# totalizer2020.net
KiCad netlist of a schematic drawn in EAGLE
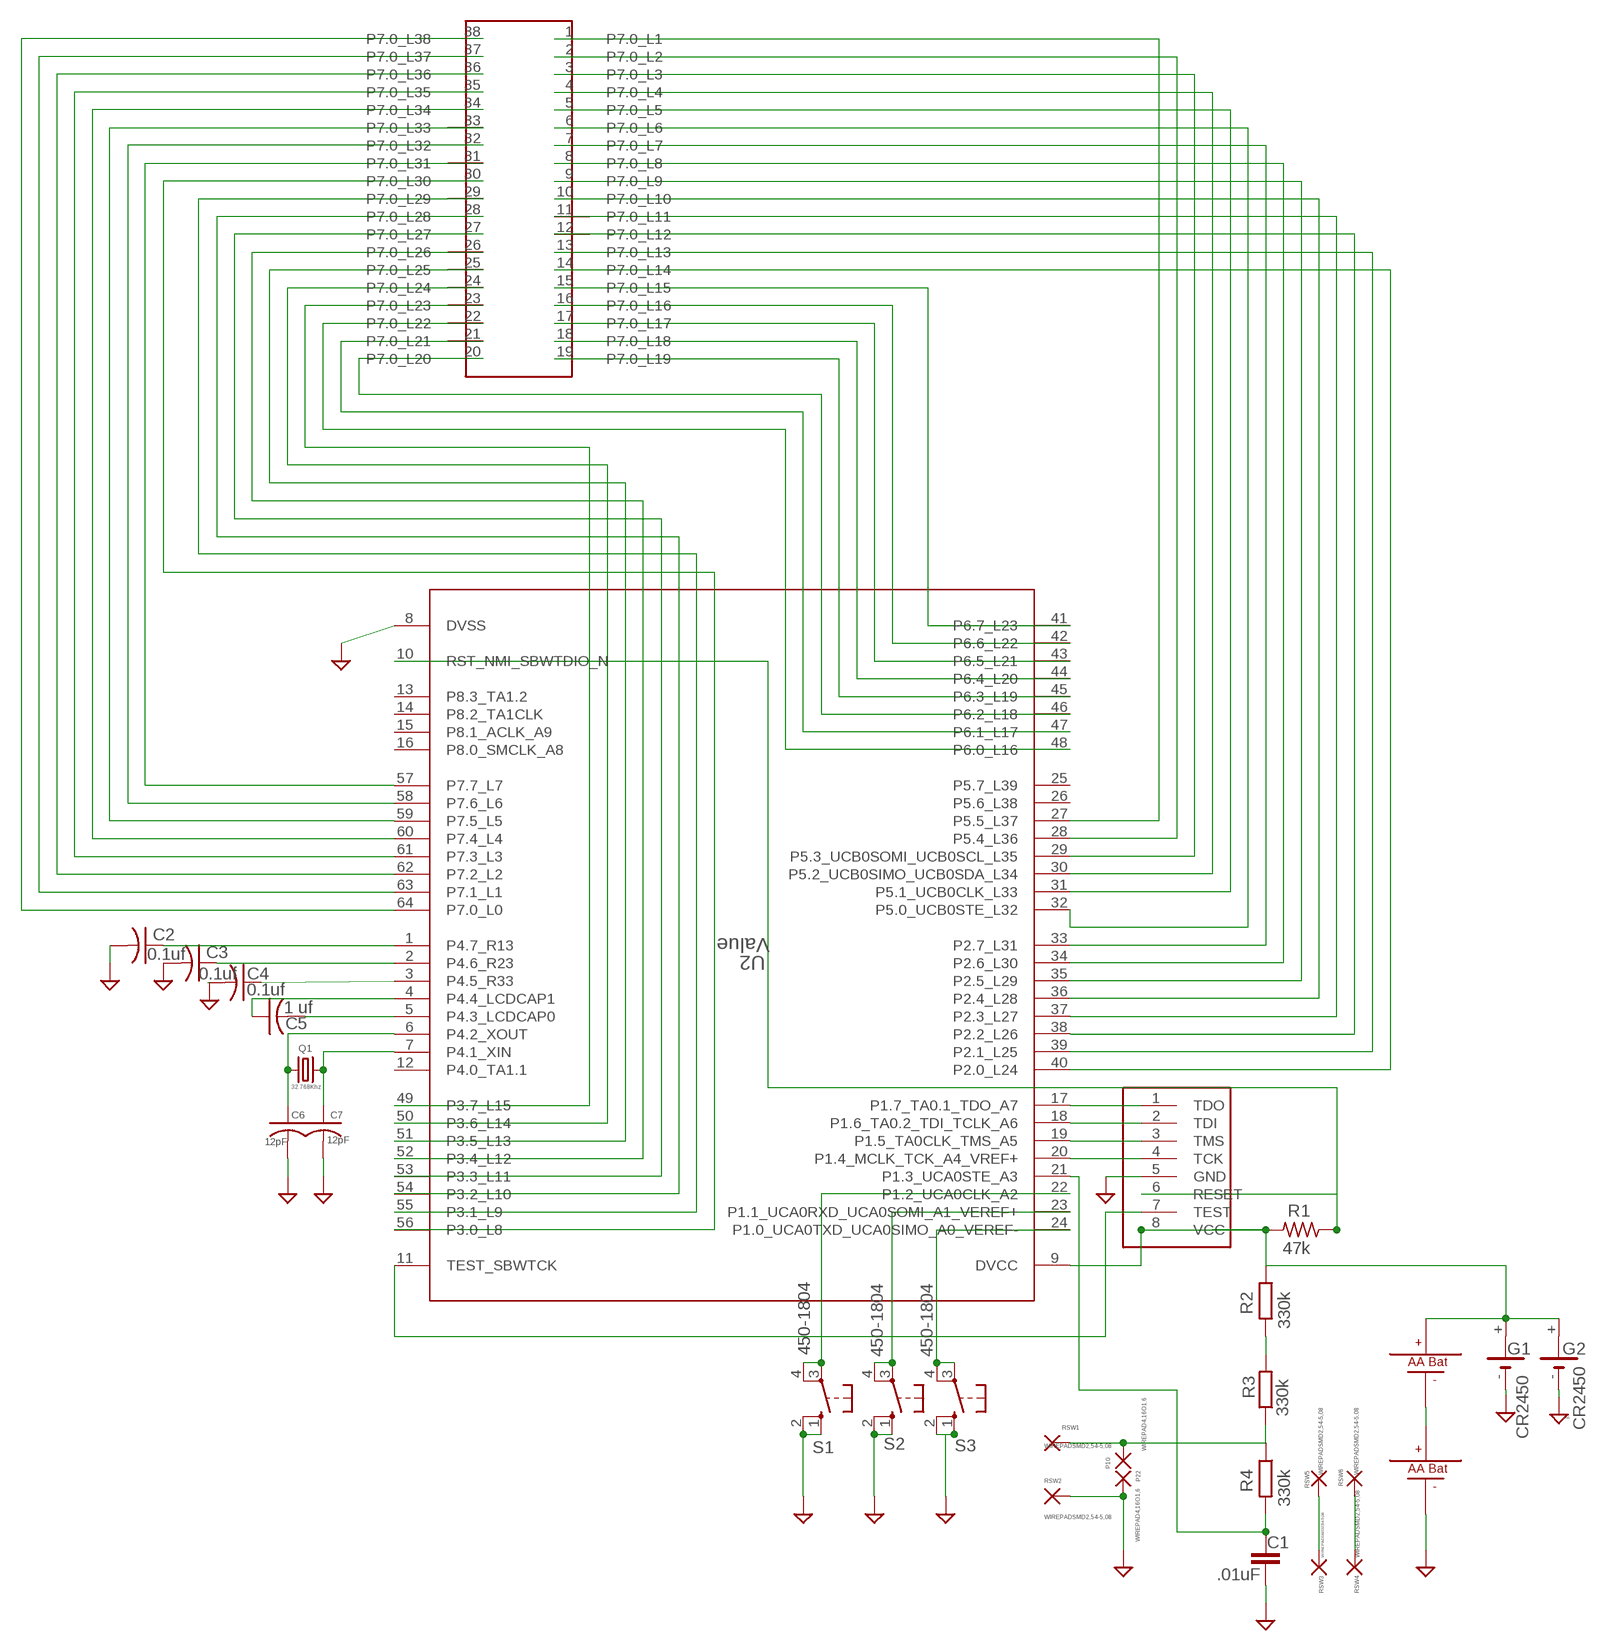
[diagram p0: schematic, sheet 1]

(export (version "E")
  (design (tool "Eeschema 10.0.6"))
  (components
    (comp (ref "8PINCONNECTOR")
      (value "JST-8JST-8")
      (footprint "eagle-import:HDRVR8W64P150_1X8_1200X350X500B")
      (libsource (lib "eagle-import") (part "JST-8JST-8"))
    )
    (comp (ref "C1")
      (value ".01uF")
      (footprint "eagle-import:C0805")
      (libsource (lib "eagle-import") (part "C-EUC0805"))
    )
    (comp (ref "C2")
      (value "0.1uf")
      (footprint "eagle-import:C0805")
      (libsource (lib "eagle-import") (part "C-USC0805"))
    )
    (comp (ref "C3")
      (value "0.1uf")
      (footprint "eagle-import:C0805")
      (libsource (lib "eagle-import") (part "C-USC0805"))
    )
    (comp (ref "C4")
      (value "0.1uf")
      (footprint "eagle-import:C0805")
      (libsource (lib "eagle-import") (part "C-USC0805"))
    )
    (comp (ref "C5")
      (value "1 uf")
      (footprint "eagle-import:C0805")
      (libsource (lib "eagle-import") (part "C-USC0805"))
    )
    (comp (ref "C6")
      (value "12pF")
      (footprint "eagle-import:C0805")
      (libsource (lib "eagle-import") (part "resistor_348_C-USC0805"))
    )
    (comp (ref "C7")
      (value "12pF")
      (footprint "eagle-import:C0805")
      (libsource (lib "eagle-import") (part "resistor_348_C-USC0805"))
    )
    (comp (ref "G1")
      (value "CR2450")
      (footprint "eagle-import:CR2430H")
      (libsource (lib "eagle-import") (part "CR2430H"))
    )
    (comp (ref "G2")
      (value "CR2450")
      (footprint "eagle-import:CR2430H")
      (libsource (lib "eagle-import") (part "CR2430H"))
    )
    (comp (ref "P10")
      (value "WIREPAD4,16O1,6")
      (footprint "eagle-import:4,16O1,6")
      (libsource (lib "eagle-import") (part "WIREPAD4,16O1,6"))
    )
    (comp (ref "P22")
      (value "WIREPAD4,16O1,6")
      (footprint "eagle-import:4,16O1,6")
      (libsource (lib "eagle-import") (part "WIREPAD4,16O1,6"))
    )
    (comp (ref "Q1")
      (value "32.768Khz")
      (footprint "eagle-import:3.2X1.5")
      (libsource (lib "eagle-import") (part "KX-327-NHT"))
    )
    (comp (ref "R1")
      (value "47k")
      (footprint "eagle-import:R0805")
      (libsource (lib "eagle-import") (part "R-US_R0805"))
    )
    (comp (ref "R2")
      (value "330k")
      (footprint "eagle-import:R0805")
      (libsource (lib "eagle-import") (part "R-R0805"))
    )
    (comp (ref "R3")
      (value "330k")
      (footprint "eagle-import:R0805")
      (libsource (lib "eagle-import") (part "R-R0805"))
    )
    (comp (ref "R4")
      (value "330k")
      (footprint "eagle-import:R0805")
      (libsource (lib "eagle-import") (part "R-R0805"))
    )
    (comp (ref "RSW1")
      (value "WIREPADSMD2,54-5,08")
      (footprint "eagle-import:SMD2,54-5,08")
      (libsource (lib "eagle-import") (part "WIREPADSMD2,54-5,08"))
    )
    (comp (ref "RSW2")
      (value "WIREPADSMD2,54-5,08")
      (footprint "eagle-import:SMD2,54-5,08")
      (libsource (lib "eagle-import") (part "WIREPADSMD2,54-5,08"))
    )
    (comp (ref "RSW3")
      (value "WIREPADSMD2,54-5,08")
      (footprint "eagle-import:SMD2,54-5,08")
      (libsource (lib "eagle-import") (part "WIREPADSMD2,54-5,08"))
    )
    (comp (ref "RSW4")
      (value "WIREPADSMD2,54-5,08")
      (footprint "eagle-import:SMD2,54-5,08")
      (libsource (lib "eagle-import") (part "WIREPADSMD2,54-5,08"))
    )
    (comp (ref "RSW5")
      (value "WIREPADSMD2,54-5,08")
      (footprint "eagle-import:SMD2,54-5,08")
      (libsource (lib "eagle-import") (part "WIREPADSMD2,54-5,08"))
    )
    (comp (ref "RSW6")
      (value "WIREPADSMD2,54-5,08")
      (footprint "eagle-import:SMD2,54-5,08")
      (libsource (lib "eagle-import") (part "WIREPADSMD2,54-5,08"))
    )
    (comp (ref "S1")
      (value "450-1804")
      (footprint "eagle-import:B3F-10XX")
      (fields (field (name "MPN") "B3F-1000"))
      (libsource (lib "eagle-import") (part "10-XX"))
    )
    (comp (ref "S2")
      (value "450-1804")
      (footprint "eagle-import:B3F-10XX")
      (fields (field (name "MPN") "B3F-1000"))
      (libsource (lib "eagle-import") (part "10-XX"))
    )
    (comp (ref "S3")
      (value "450-1804")
      (footprint "eagle-import:B3F-10XX")
      (fields (field (name "MPN") "B3F-1000"))
      (libsource (lib "eagle-import") (part "10-XX"))
    )
    (comp (ref "U$1")
      (value "LCD-38LCD-38")
      (footprint "eagle-import:DIP7140W53P200L5505H450Q38B")
      (libsource (lib "eagle-import") (part "LCD-38LCD-38"))
    )
    (comp (ref "U$2")
      (value "AA_BATTERY")
      (footprint "eagle-import:AA_BATTERY")
      (libsource (lib "eagle-import") (part "AA_BATTERY"))
    )
    (comp (ref "U$3")
      (value "AA_BATTERY")
      (footprint "eagle-import:AA_BATTERY")
      (libsource (lib "eagle-import") (part "AA_BATTERY"))
    )
    (comp (ref "U2")
      (value "Value")
      (footprint "eagle-import:PM0064A_N")
      (fields
        (field (name "ALTERNATEPARTNUMBER") "MSP430FR4133IPM")
        (field (name "MANUFACTURER") "Texas Instruments")
        (field (name "PARTNUMBER") "MSP430FR4133IPMR")
      )
      (libsource (lib "eagle-import") (part "MSP430FR4133IPMR"))
    )
  )
  (nets
    (net (code "1") (name "GND") (class "Default")
      (node (ref "8PINCONNECTOR") (pin "5") (pinfunction "GND_5") (pintype "power_in"))
      (node (ref "C1") (pin "1") (pinfunction "1_1") (pintype "passive"))
      (node (ref "C2") (pin "2") (pinfunction "2_2") (pintype "passive"))
      (node (ref "C3") (pin "2") (pinfunction "2_2") (pintype "passive"))
      (node (ref "C4") (pin "2") (pinfunction "2_2") (pintype "passive"))
      (node (ref "C6") (pin "2") (pinfunction "2_2") (pintype "passive"))
      (node (ref "C7") (pin "2") (pinfunction "2_2") (pintype "passive"))
      (node (ref "G1") (pin "-") (pinfunction "-_-") (pintype "passive"))
      (node (ref "G2") (pin "-") (pinfunction "-_-") (pintype "passive"))
      (node (ref "P22") (pin "1") (pinfunction "P_1") (pintype "passive"))
      (node (ref "RSW2") (pin "1") (pinfunction "P_1") (pintype "passive"))
      (node (ref "S1") (pin "1") (pinfunction "S_1") (pintype "passive"))
      (node (ref "S1") (pin "2") (pinfunction "S1_2") (pintype "passive"))
      (node (ref "S2") (pin "1") (pinfunction "S_1") (pintype "passive"))
      (node (ref "S2") (pin "2") (pinfunction "S1_2") (pintype "passive"))
      (node (ref "S3") (pin "1") (pinfunction "S_1") (pintype "passive"))
      (node (ref "S3") (pin "2") (pinfunction "S1_2") (pintype "passive"))
      (node (ref "U$3") (pin "3") (pinfunction "BAT_-_3") (pintype "power_in"))
      (node (ref "U$3") (pin "4") (pinfunction "BAT_-_4") (pintype "power_in"))
      (node (ref "U2") (pin "8") (pinfunction "DVSS_8") (pintype "power_in"))
    )
    (net (code "2") (name "Net-(8PINCONNECTOR-RESET)") (class "Default")
      (node (ref "8PINCONNECTOR") (pin "6") (pinfunction "RESET_6") (pintype "bidirectional"))
      (node (ref "R1") (pin "1") (pinfunction "1_1") (pintype "passive"))
      (node (ref "U2") (pin "10") (pinfunction "RST_NMI_SBWTDIO_N_10") (pintype "input"))
    )
    (net (code "3") (name "Net-(8PINCONNECTOR-TCK)") (class "Default")
      (node (ref "8PINCONNECTOR") (pin "4") (pinfunction "TCK_4") (pintype "bidirectional"))
      (node (ref "U2") (pin "20") (pinfunction "P1.4_MCLK_TCK_A4_VREF+_20") (pintype "bidirectional"))
    )
    (net (code "4") (name "Net-(8PINCONNECTOR-TDI)") (class "Default")
      (node (ref "8PINCONNECTOR") (pin "2") (pinfunction "TDI_2") (pintype "bidirectional"))
      (node (ref "U2") (pin "18") (pinfunction "P1.6_TA0.2_TDI_TCLK_A6_18") (pintype "bidirectional"))
    )
    (net (code "5") (name "Net-(8PINCONNECTOR-TDO)") (class "Default")
      (node (ref "8PINCONNECTOR") (pin "1") (pinfunction "TDO_1") (pintype "bidirectional"))
      (node (ref "U2") (pin "17") (pinfunction "P1.7_TA0.1_TDO_A7_17") (pintype "bidirectional"))
    )
    (net (code "6") (name "Net-(8PINCONNECTOR-TEST)") (class "Default")
      (node (ref "8PINCONNECTOR") (pin "7") (pinfunction "TEST_7") (pintype "bidirectional"))
      (node (ref "U2") (pin "11") (pinfunction "TEST_SBWTCK_11") (pintype "input"))
    )
    (net (code "7") (name "Net-(8PINCONNECTOR-TMS)") (class "Default")
      (node (ref "8PINCONNECTOR") (pin "3") (pinfunction "TMS_3") (pintype "bidirectional"))
      (node (ref "U2") (pin "19") (pinfunction "P1.5_TA0CLK_TMS_A5_19") (pintype "bidirectional"))
    )
    (net (code "8") (name "Net-(8PINCONNECTOR-VCC)") (class "Default")
      (node (ref "8PINCONNECTOR") (pin "8") (pinfunction "VCC_8") (pintype "power_in"))
      (node (ref "G1") (pin "+") (pinfunction "+_+") (pintype "passive"))
      (node (ref "G2") (pin "+") (pinfunction "+_+") (pintype "passive"))
      (node (ref "R1") (pin "2") (pinfunction "2_2") (pintype "passive"))
      (node (ref "R2") (pin "1") (pinfunction "1_1") (pintype "passive"))
      (node (ref "U$2") (pin "2") (pinfunction "BAT_+_2") (pintype "power_in"))
      (node (ref "U$2") (pin "P1") (pinfunction "BAT_+_P1") (pintype "power_in"))
      (node (ref "U2") (pin "9") (pinfunction "DVCC_9") (pintype "power_in"))
    )
    (net (code "9") (name "Net-(P10-P)") (class "Default")
      (node (ref "P10") (pin "1") (pinfunction "P_1") (pintype "passive"))
      (node (ref "R3") (pin "1") (pinfunction "1_1") (pintype "passive"))
      (node (ref "R4") (pin "1") (pinfunction "1_1") (pintype "passive"))
      (node (ref "RSW1") (pin "1") (pinfunction "P_1") (pintype "passive"))
    )
    (net (code "10") (name "Net-(R2-Pad2)") (class "Default")
      (node (ref "R2") (pin "2") (pinfunction "2_2") (pintype "passive"))
      (node (ref "R3") (pin "2") (pinfunction "2_2") (pintype "passive"))
    )
    (net (code "11") (name "Net-(RSW3-P)") (class "Default")
      (node (ref "RSW3") (pin "1") (pinfunction "P_1") (pintype "passive"))
      (node (ref "RSW5") (pin "1") (pinfunction "P_1") (pintype "passive"))
    )
    (net (code "12") (name "Net-(RSW4-P)") (class "Default")
      (node (ref "RSW4") (pin "1") (pinfunction "P_1") (pintype "passive"))
      (node (ref "RSW6") (pin "1") (pinfunction "P_1") (pintype "passive"))
    )
    (net (code "13") (name "Net-(S1-P)") (class "Default")
      (node (ref "S1") (pin "3") (pinfunction "P_3") (pintype "passive"))
      (node (ref "S1") (pin "4") (pinfunction "P1_4") (pintype "passive"))
      (node (ref "U2") (pin "22") (pinfunction "P1.2_UCA0CLK_A2_22") (pintype "bidirectional"))
    )
    (net (code "14") (name "Net-(S2-P)") (class "Default")
      (node (ref "S2") (pin "3") (pinfunction "P_3") (pintype "passive"))
      (node (ref "S2") (pin "4") (pinfunction "P1_4") (pintype "passive"))
      (node (ref "U2") (pin "23") (pinfunction "P1.1_UCA0RXD_UCA0SOMI_A1_VEREF+_23") (pintype "bidirectional"))
    )
    (net (code "15") (name "Net-(S3-P)") (class "Default")
      (node (ref "S3") (pin "3") (pinfunction "P_3") (pintype "passive"))
      (node (ref "S3") (pin "4") (pinfunction "P1_4") (pintype "passive"))
      (node (ref "U2") (pin "24") (pinfunction "P1.0_UCA0TXD_UCA0SIMO_A0_VEREF-_24") (pintype "bidirectional"))
    )
    (net (code "16") (name "Net-(U$1-P7.0_L1)") (class "Default")
      (node (ref "U$1") (pin "1") (pinfunction "P7.0_L1_1") (pintype "bidirectional"))
      (node (ref "U2") (pin "27") (pinfunction "P5.5_L37_27") (pintype "bidirectional"))
    )
    (net (code "17") (name "Net-(U$1-P7.0_L2)") (class "Default")
      (node (ref "U$1") (pin "2") (pinfunction "P7.0_L2_2") (pintype "bidirectional"))
      (node (ref "U2") (pin "28") (pinfunction "P5.4_L36_28") (pintype "bidirectional"))
    )
    (net (code "18") (name "Net-(U$1-P7.0_L3)") (class "Default")
      (node (ref "U$1") (pin "3") (pinfunction "P7.0_L3_3") (pintype "bidirectional"))
      (node (ref "U2") (pin "29") (pinfunction "P5.3_UCB0SOMI_UCB0SCL_L35_29") (pintype "bidirectional"))
    )
    (net (code "19") (name "Net-(U$1-P7.0_L4)") (class "Default")
      (node (ref "U$1") (pin "4") (pinfunction "P7.0_L4_4") (pintype "bidirectional"))
      (node (ref "U2") (pin "30") (pinfunction "P5.2_UCB0SIMO_UCB0SDA_L34_30") (pintype "bidirectional"))
    )
    (net (code "20") (name "Net-(U$1-P7.0_L5)") (class "Default")
      (node (ref "U$1") (pin "5") (pinfunction "P7.0_L5_5") (pintype "bidirectional"))
      (node (ref "U2") (pin "31") (pinfunction "P5.1_UCB0CLK_L33_31") (pintype "bidirectional"))
    )
    (net (code "21") (name "Net-(U$1-P7.0_L6)") (class "Default")
      (node (ref "U$1") (pin "6") (pinfunction "P7.0_L6_6") (pintype "bidirectional"))
      (node (ref "U2") (pin "32") (pinfunction "P5.0_UCB0STE_L32_32") (pintype "bidirectional"))
    )
    (net (code "22") (name "Net-(U$1-P7.0_L7)") (class "Default")
      (node (ref "U$1") (pin "7") (pinfunction "P7.0_L7_7") (pintype "bidirectional"))
      (node (ref "U2") (pin "33") (pinfunction "P2.7_L31_33") (pintype "bidirectional"))
    )
    (net (code "23") (name "Net-(U$1-P7.0_L8)") (class "Default")
      (node (ref "U$1") (pin "8") (pinfunction "P7.0_L8_8") (pintype "bidirectional"))
      (node (ref "U2") (pin "34") (pinfunction "P2.6_L30_34") (pintype "bidirectional"))
    )
    (net (code "24") (name "Net-(U$1-P7.0_L9)") (class "Default")
      (node (ref "U$1") (pin "9") (pinfunction "P7.0_L9_9") (pintype "bidirectional"))
      (node (ref "U2") (pin "35") (pinfunction "P2.5_L29_35") (pintype "bidirectional"))
    )
    (net (code "25") (name "Net-(U$1-P7.0_L10)") (class "Default")
      (node (ref "U$1") (pin "10") (pinfunction "P7.0_L10_10") (pintype "bidirectional"))
      (node (ref "U2") (pin "36") (pinfunction "P2.4_L28_36") (pintype "bidirectional"))
    )
    (net (code "26") (name "Net-(U$1-P7.0_L11)") (class "Default")
      (node (ref "U$1") (pin "11") (pinfunction "P7.0_L11_11") (pintype "bidirectional"))
      (node (ref "U2") (pin "37") (pinfunction "P2.3_L27_37") (pintype "bidirectional"))
    )
    (net (code "27") (name "Net-(U$1-P7.0_L12)") (class "Default")
      (node (ref "U$1") (pin "12") (pinfunction "P7.0_L12_12") (pintype "bidirectional"))
      (node (ref "U2") (pin "38") (pinfunction "P2.2_L26_38") (pintype "bidirectional"))
    )
    (net (code "28") (name "Net-(U$1-P7.0_L13)") (class "Default")
      (node (ref "U$1") (pin "13") (pinfunction "P7.0_L13_13") (pintype "bidirectional"))
      (node (ref "U2") (pin "39") (pinfunction "P2.1_L25_39") (pintype "bidirectional"))
    )
    (net (code "29") (name "Net-(U$1-P7.0_L14)") (class "Default")
      (node (ref "U$1") (pin "14") (pinfunction "P7.0_L14_14") (pintype "bidirectional"))
      (node (ref "U2") (pin "40") (pinfunction "P2.0_L24_40") (pintype "bidirectional"))
    )
    (net (code "30") (name "Net-(U$1-P7.0_L15)") (class "Default")
      (node (ref "U$1") (pin "15") (pinfunction "P7.0_L15_15") (pintype "bidirectional"))
      (node (ref "U2") (pin "41") (pinfunction "P6.7_L23_41") (pintype "bidirectional"))
    )
    (net (code "31") (name "Net-(U$1-P7.0_L16)") (class "Default")
      (node (ref "U$1") (pin "16") (pinfunction "P7.0_L16_16") (pintype "bidirectional"))
      (node (ref "U2") (pin "42") (pinfunction "P6.6_L22_42") (pintype "bidirectional"))
    )
    (net (code "32") (name "Net-(U$1-P7.0_L17)") (class "Default")
      (node (ref "U$1") (pin "17") (pinfunction "P7.0_L17_17") (pintype "bidirectional"))
      (node (ref "U2") (pin "43") (pinfunction "P6.5_L21_43") (pintype "bidirectional"))
    )
    (net (code "33") (name "Net-(U$1-P7.0_L18)") (class "Default")
      (node (ref "U$1") (pin "18") (pinfunction "P7.0_L18_18") (pintype "bidirectional"))
      (node (ref "U2") (pin "44") (pinfunction "P6.4_L20_44") (pintype "bidirectional"))
    )
    (net (code "34") (name "Net-(U$1-P7.0_L19)") (class "Default")
      (node (ref "U$1") (pin "19") (pinfunction "P7.0_L19_19") (pintype "bidirectional"))
      (node (ref "U2") (pin "45") (pinfunction "P6.3_L19_45") (pintype "bidirectional"))
    )
    (net (code "35") (name "Net-(U$1-P7.0_L20)") (class "Default")
      (node (ref "U$1") (pin "20") (pinfunction "P7.0_L20_20") (pintype "bidirectional"))
      (node (ref "U2") (pin "46") (pinfunction "P6.2_L18_46") (pintype "bidirectional"))
    )
    (net (code "36") (name "Net-(U$1-P7.0_L21)") (class "Default")
      (node (ref "U$1") (pin "21") (pinfunction "P7.0_L21_21") (pintype "bidirectional"))
      (node (ref "U2") (pin "47") (pinfunction "P6.1_L17_47") (pintype "bidirectional"))
    )
    (net (code "37") (name "Net-(U$1-P7.0_L22)") (class "Default")
      (node (ref "U$1") (pin "22") (pinfunction "P7.0_L22_22") (pintype "bidirectional"))
      (node (ref "U2") (pin "48") (pinfunction "P6.0_L16_48") (pintype "bidirectional"))
    )
    (net (code "38") (name "Net-(U$1-P7.0_L23)") (class "Default")
      (node (ref "U$1") (pin "23") (pinfunction "P7.0_L23_23") (pintype "bidirectional"))
      (node (ref "U2") (pin "49") (pinfunction "P3.7_L15_49") (pintype "bidirectional"))
    )
    (net (code "39") (name "Net-(U$1-P7.0_L24)") (class "Default")
      (node (ref "U$1") (pin "24") (pinfunction "P7.0_L24_24") (pintype "bidirectional"))
      (node (ref "U2") (pin "50") (pinfunction "P3.6_L14_50") (pintype "bidirectional"))
    )
    (net (code "40") (name "Net-(U$1-P7.0_L25)") (class "Default")
      (node (ref "U$1") (pin "25") (pinfunction "P7.0_L25_25") (pintype "bidirectional"))
      (node (ref "U2") (pin "51") (pinfunction "P3.5_L13_51") (pintype "bidirectional"))
    )
    (net (code "41") (name "Net-(U$1-P7.0_L26)") (class "Default")
      (node (ref "U$1") (pin "26") (pinfunction "P7.0_L26_26") (pintype "bidirectional"))
      (node (ref "U2") (pin "52") (pinfunction "P3.4_L12_52") (pintype "bidirectional"))
    )
    (net (code "42") (name "Net-(U$1-P7.0_L27)") (class "Default")
      (node (ref "U$1") (pin "27") (pinfunction "P7.0_L27_27") (pintype "bidirectional"))
      (node (ref "U2") (pin "53") (pinfunction "P3.3_L11_53") (pintype "bidirectional"))
    )
    (net (code "43") (name "Net-(U$1-P7.0_L28)") (class "Default")
      (node (ref "U$1") (pin "28") (pinfunction "P7.0_L28_28") (pintype "bidirectional"))
      (node (ref "U2") (pin "54") (pinfunction "P3.2_L10_54") (pintype "bidirectional"))
    )
    (net (code "44") (name "Net-(U$1-P7.0_L29)") (class "Default")
      (node (ref "U$1") (pin "29") (pinfunction "P7.0_L29_29") (pintype "bidirectional"))
      (node (ref "U2") (pin "55") (pinfunction "P3.1_L9_55") (pintype "bidirectional"))
    )
    (net (code "45") (name "Net-(U$1-P7.0_L30)") (class "Default")
      (node (ref "U$1") (pin "30") (pinfunction "P7.0_L30_30") (pintype "bidirectional"))
      (node (ref "U2") (pin "56") (pinfunction "P3.0_L8_56") (pintype "bidirectional"))
    )
    (net (code "46") (name "Net-(U$1-P7.0_L31)") (class "Default")
      (node (ref "U$1") (pin "31") (pinfunction "P7.0_L31_31") (pintype "bidirectional"))
      (node (ref "U2") (pin "57") (pinfunction "P7.7_L7_57") (pintype "bidirectional"))
    )
    (net (code "47") (name "Net-(U$1-P7.0_L32)") (class "Default")
      (node (ref "U$1") (pin "32") (pinfunction "P7.0_L32_32") (pintype "bidirectional"))
      (node (ref "U2") (pin "58") (pinfunction "P7.6_L6_58") (pintype "bidirectional"))
    )
    (net (code "48") (name "Net-(U$1-P7.0_L33)") (class "Default")
      (node (ref "U$1") (pin "33") (pinfunction "P7.0_L33_33") (pintype "bidirectional"))
      (node (ref "U2") (pin "59") (pinfunction "P7.5_L5_59") (pintype "bidirectional"))
    )
    (net (code "49") (name "Net-(U$1-P7.0_L34)") (class "Default")
      (node (ref "U$1") (pin "34") (pinfunction "P7.0_L34_34") (pintype "bidirectional"))
      (node (ref "U2") (pin "60") (pinfunction "P7.4_L4_60") (pintype "bidirectional"))
    )
    (net (code "50") (name "Net-(U$1-P7.0_L35)") (class "Default")
      (node (ref "U$1") (pin "35") (pinfunction "P7.0_L35_35") (pintype "bidirectional"))
      (node (ref "U2") (pin "61") (pinfunction "P7.3_L3_61") (pintype "bidirectional"))
    )
    (net (code "51") (name "Net-(U$1-P7.0_L36)") (class "Default")
      (node (ref "U$1") (pin "36") (pinfunction "P7.0_L36_36") (pintype "bidirectional"))
      (node (ref "U2") (pin "62") (pinfunction "P7.2_L2_62") (pintype "bidirectional"))
    )
    (net (code "52") (name "Net-(U$1-P7.0_L37)") (class "Default")
      (node (ref "U$1") (pin "37") (pinfunction "P7.0_L37_37") (pintype "bidirectional"))
      (node (ref "U2") (pin "63") (pinfunction "P7.1_L1_63") (pintype "bidirectional"))
    )
    (net (code "53") (name "Net-(U$1-P7.0_L38)") (class "Default")
      (node (ref "U$1") (pin "38") (pinfunction "P7.0_L38_38") (pintype "bidirectional"))
      (node (ref "U2") (pin "64") (pinfunction "P7.0_L0_64") (pintype "bidirectional"))
    )
    (net (code "54") (name "Net-(U$2-BAT_--Pad3)") (class "Default")
      (node (ref "U$2") (pin "3") (pinfunction "BAT_-_3") (pintype "power_in"))
      (node (ref "U$2") (pin "4") (pinfunction "BAT_-_4") (pintype "power_in"))
      (node (ref "U$3") (pin "2") (pinfunction "BAT_+_2") (pintype "power_in"))
      (node (ref "U$3") (pin "P1") (pinfunction "BAT_+_P1") (pintype "power_in"))
    )
    (net (code "55") (name "Net-(U2-P1.3_UCA0STE_A3)") (class "Default")
      (node (ref "C1") (pin "2") (pinfunction "2_2") (pintype "passive"))
      (node (ref "R4") (pin "2") (pinfunction "2_2") (pintype "passive"))
      (node (ref "U2") (pin "21") (pinfunction "P1.3_UCA0STE_A3_21") (pintype "bidirectional"))
    )
    (net (code "56") (name "Net-(U2-P4.1_XIN)") (class "Default")
      (node (ref "C7") (pin "1") (pinfunction "1_1") (pintype "passive"))
      (node (ref "Q1") (pin "2") (pinfunction "2_2") (pintype "passive"))
      (node (ref "U2") (pin "7") (pinfunction "P4.1_XIN_7") (pintype "bidirectional"))
    )
    (net (code "57") (name "Net-(U2-P4.2_XOUT)") (class "Default")
      (node (ref "C6") (pin "1") (pinfunction "1_1") (pintype "passive"))
      (node (ref "Q1") (pin "1") (pinfunction "1_1") (pintype "passive"))
      (node (ref "U2") (pin "6") (pinfunction "P4.2_XOUT_6") (pintype "bidirectional"))
    )
    (net (code "58") (name "Net-(U2-P4.3_LCDCAP0)") (class "Default")
      (node (ref "C5") (pin "2") (pinfunction "2_2") (pintype "passive"))
      (node (ref "U2") (pin "5") (pinfunction "P4.3_LCDCAP0_5") (pintype "bidirectional"))
    )
    (net (code "59") (name "Net-(U2-P4.4_LCDCAP1)") (class "Default")
      (node (ref "C5") (pin "1") (pinfunction "1_1") (pintype "passive"))
      (node (ref "U2") (pin "4") (pinfunction "P4.4_LCDCAP1_4") (pintype "bidirectional"))
    )
    (net (code "60") (name "Net-(U2-P4.5_R33)") (class "Default")
      (node (ref "C4") (pin "1") (pinfunction "1_1") (pintype "passive"))
      (node (ref "U2") (pin "3") (pinfunction "P4.5_R33_3") (pintype "bidirectional"))
    )
    (net (code "61") (name "Net-(U2-P4.6_R23)") (class "Default")
      (node (ref "C3") (pin "1") (pinfunction "1_1") (pintype "passive"))
      (node (ref "U2") (pin "2") (pinfunction "P4.6_R23_2") (pintype "bidirectional"))
    )
    (net (code "62") (name "Net-(U2-P4.7_R13)") (class "Default")
      (node (ref "C2") (pin "1") (pinfunction "1_1") (pintype "passive"))
      (node (ref "U2") (pin "1") (pinfunction "P4.7_R13_1") (pintype "bidirectional"))
    )
    (net (code "63") (name "unconnected-(G1-+-Pad+@1)") (class "Default")
      (node (ref "G1") (pin "+@1") (pinfunction "+_+@1") (pintype "passive"))
    )
    (net (code "64") (name "unconnected-(G2-+-Pad+@1)") (class "Default")
      (node (ref "G2") (pin "+@1") (pinfunction "+_+@1") (pintype "passive"))
    )
    (net (code "65") (name "unconnected-(U2-P4.0_TA1.1-Pad12)") (class "Default")
      (node (ref "U2") (pin "12") (pinfunction "P4.0_TA1.1_12") (pintype "bidirectional"))
    )
    (net (code "66") (name "unconnected-(U2-P5.6_L38-Pad26)") (class "Default")
      (node (ref "U2") (pin "26") (pinfunction "P5.6_L38_26") (pintype "bidirectional"))
    )
    (net (code "67") (name "unconnected-(U2-P5.7_L39-Pad25)") (class "Default")
      (node (ref "U2") (pin "25") (pinfunction "P5.7_L39_25") (pintype "bidirectional"))
    )
    (net (code "68") (name "unconnected-(U2-P8.0_SMCLK_A8-Pad16)") (class "Default")
      (node (ref "U2") (pin "16") (pinfunction "P8.0_SMCLK_A8_16") (pintype "bidirectional"))
    )
    (net (code "69") (name "unconnected-(U2-P8.1_ACLK_A9-Pad15)") (class "Default")
      (node (ref "U2") (pin "15") (pinfunction "P8.1_ACLK_A9_15") (pintype "bidirectional"))
    )
    (net (code "70") (name "unconnected-(U2-P8.2_TA1CLK-Pad14)") (class "Default")
      (node (ref "U2") (pin "14") (pinfunction "P8.2_TA1CLK_14") (pintype "bidirectional"))
    )
    (net (code "71") (name "unconnected-(U2-P8.3_TA1.2-Pad13)") (class "Default")
      (node (ref "U2") (pin "13") (pinfunction "P8.3_TA1.2_13") (pintype "bidirectional"))
    )
  )
)
